# LTC6803.net
KiCad netlist of a schematic drawn in Altium Designer
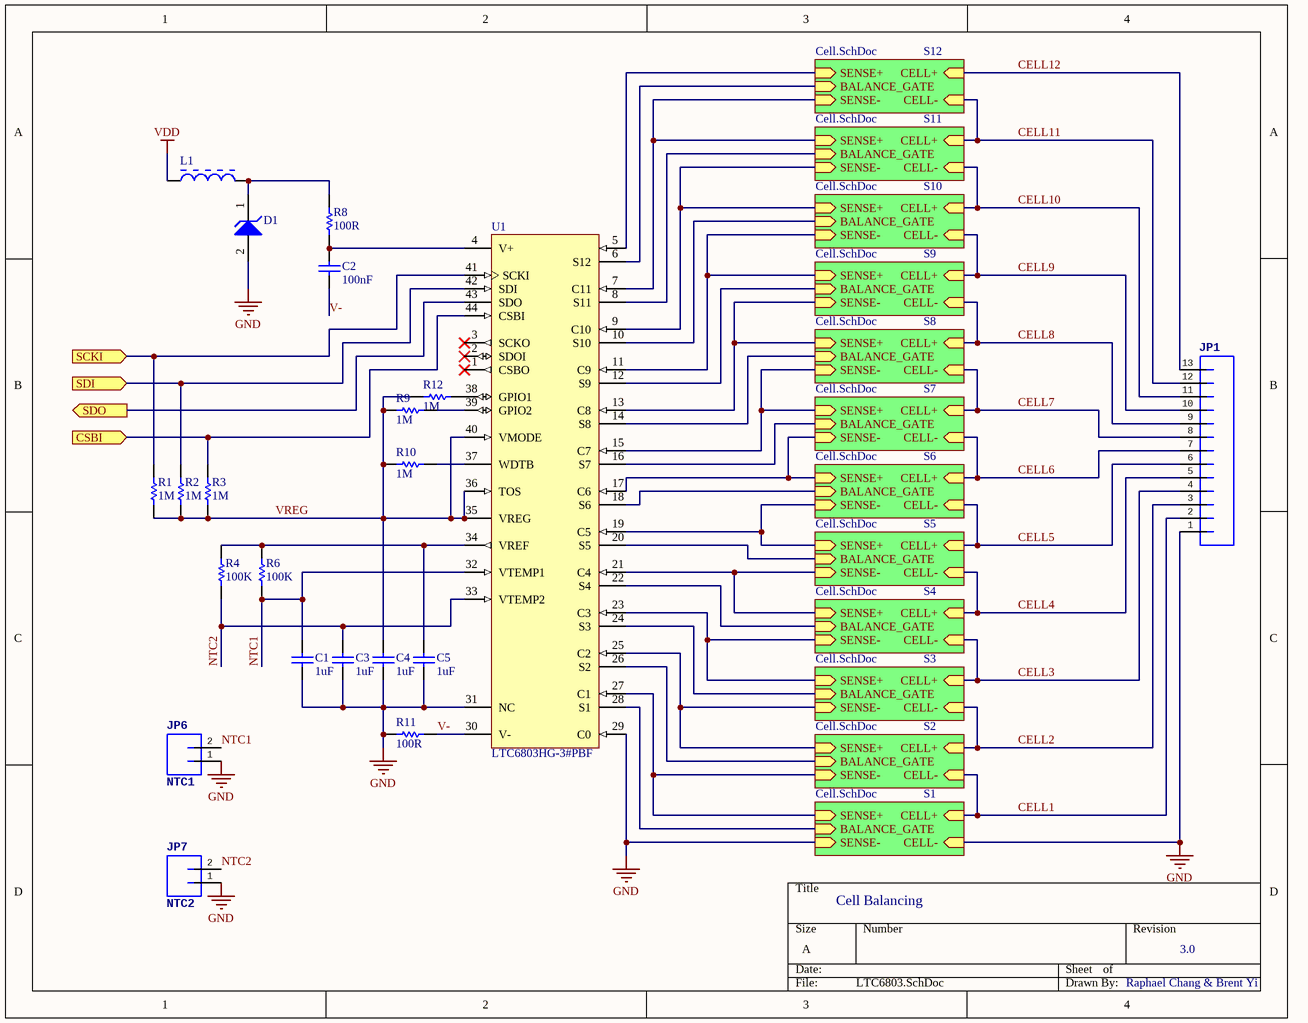
[diagram p0: LTC6803.SchDoc]

(export (version "E")
  (design (tool "Eeschema 10.0.6"))
  (components
    (comp (ref "C1")
      (value "1uF")
      (footprint "CAPC0603(1608)100_N")
      (description "CAP 1uF 6.3V Â±10% 0603 (1608 Metric) Thickness 1mm SMD")
      (fields (field (name "TOLERANCE") "Â±10%"))
      (libsource (lib "Altium Content Vault") (part "CAP"))
    )
    (comp (ref "C2")
      (value "100nF")
      (footprint "CAPC0603(1608)100_L")
      (description "CAP 100nF 100V Â±10% 0603 (1608 Metric) Thickness 1mm SMD")
      (fields (field (name "TOLERANCE") "Â±10%"))
      (libsource (lib "Altium Content Vault") (part "CAP"))
    )
    (comp (ref "C3")
      (value "1uF")
      (footprint "CAPC0603(1608)100_N")
      (description "CAP 1uF 6.3V Â±10% 0603 (1608 Metric) Thickness 1mm SMD")
      (fields (field (name "TOLERANCE") "Â±10%"))
      (libsource (lib "Altium Content Vault") (part "CAP"))
    )
    (comp (ref "C4")
      (value "1uF")
      (footprint "CAPC0603(1608)100_N")
      (description "CAP 1uF 6.3V Â±10% 0603 (1608 Metric) Thickness 1mm SMD")
      (fields (field (name "TOLERANCE") "Â±10%"))
      (libsource (lib "Altium Content Vault") (part "CAP"))
    )
    (comp (ref "C5")
      (value "1uF")
      (footprint "CAPC0603(1608)100_N")
      (description "CAP 1uF 6.3V Â±10% 0603 (1608 Metric) Thickness 1mm SMD")
      (fields (field (name "TOLERANCE") "Â±10%"))
      (libsource (lib "Altium Content Vault") (part "CAP"))
    )
    (comp (ref "D1") (value "~") (footprint "SOD-123") (libsource (lib "Components") (part "CMHZ5265B")))
    (comp (ref "JP1")
      (value "~")
      (footprint "JST-13-PTH-VERT")
      (libsource (lib "Components") (part "JST_XH_13"))
    )
    (comp (ref "JP6")
      (value "NTC1")
      (footprint "JST-2-PTH-VERT")
      (libsource (lib "Components") (part "JST_2_VERT"))
    )
    (comp (ref "JP7")
      (value "NTC2")
      (footprint "JST-2-PTH-VERT")
      (libsource (lib "Components") (part "JST_2_VERT"))
    )
    (comp (ref "L1")
      (value "~")
      (footprint "MURA-BLM31-B60-CHIP-2_V3")
      (libsource (lib "Components") (part "MURA-FB-2"))
    )
    (comp (ref "R1")
      (value "1M")
      (footprint "RESC0603(1608)_L")
      (description "1M 0.1W 1% 0603 (1608 Metric)  SMD")
      (fields (field (name "POWER") "0.1 W") (field (name "TOLERANCE") "1 %"))
      (libsource (lib "Altium Content Vault") (part "RES"))
    )
    (comp (ref "R2")
      (value "1M")
      (footprint "RESC0603(1608)_L")
      (description "1M 0.1W 1% 0603 (1608 Metric)  SMD")
      (fields (field (name "POWER") "0.1 W") (field (name "TOLERANCE") "1 %"))
      (libsource (lib "Altium Content Vault") (part "RES"))
    )
    (comp (ref "R3")
      (value "1M")
      (footprint "RESC0603(1608)_L")
      (description "1M 0.1W 1% 0603 (1608 Metric)  SMD")
      (fields (field (name "POWER") "0.1 W") (field (name "TOLERANCE") "1 %"))
      (libsource (lib "Altium Content Vault") (part "RES"))
    )
    (comp (ref "R4")
      (value "100K")
      (footprint "RESC0603(1608)_N")
      (description "100K 0.1W 5% 0603 (1608 Metric)  SMD")
      (fields (field (name "TOLERANCE") "5 %") (field (name "POWER") "0.1 W"))
      (libsource (lib "Altium Content Vault") (part "RES"))
    )
    (comp (ref "R6")
      (value "100K")
      (footprint "RESC0603(1608)_N")
      (description "100K 0.1W 5% 0603 (1608 Metric)  SMD")
      (fields (field (name "TOLERANCE") "5 %") (field (name "POWER") "0.1 W"))
      (libsource (lib "Altium Content Vault") (part "RES"))
    )
    (comp (ref "R8")
      (value "100R")
      (footprint "RESC0603(1608)_L")
      (description "100R 0.1W 5% 0603 (1608 Metric)  SMD")
      (fields (field (name "TOLERANCE") "5 %") (field (name "POWER") "0.1 W"))
      (libsource (lib "Altium Content Vault") (part "CMP-1012-00050-1"))
    )
    (comp (ref "R9")
      (value "1M")
      (footprint "RESC0603(1608)_L")
      (description "1M 0.1W 1% 0603 (1608 Metric)  SMD")
      (fields (field (name "POWER") "0.1 W") (field (name "TOLERANCE") "1 %"))
      (libsource (lib "Altium Content Vault") (part "RES"))
    )
    (comp (ref "R10")
      (value "1M")
      (footprint "RESC0603(1608)_L")
      (description "1M 0.1W 1% 0603 (1608 Metric)  SMD")
      (fields (field (name "POWER") "0.1 W") (field (name "TOLERANCE") "1 %"))
      (libsource (lib "Altium Content Vault") (part "RES"))
    )
    (comp (ref "R11")
      (value "100R")
      (footprint "RESC0603(1608)_L")
      (description "100R 0.1W 5% 0603 (1608 Metric)  SMD")
      (fields (field (name "TOLERANCE") "5 %") (field (name "POWER") "0.1 W"))
      (libsource (lib "Altium Content Vault") (part "RES"))
    )
    (comp (ref "R12")
      (value "1M")
      (footprint "RESC0603(1608)_L")
      (description "1M 0.1W 1% 0603 (1608 Metric)  SMD")
      (fields (field (name "POWER") "0.1 W") (field (name "TOLERANCE") "1 %"))
      (libsource (lib "Altium Content Vault") (part "RES"))
    )
    (comp (ref "U1")
      (value "LTC6803HG-3#PBF")
      (footprint "LT-G-44_L")
      (description "Multicell Battery Stack Monitor, 60 V Vin MAX, 44-pin SOP (G-44), -40 to 125 degC, Pb-Free")
      (fields (field (name "MANUFACTURER") "Linear Technology"))
      (libsource (lib "Altium Content Vault") (part "LT-LTC6803-3-G-44"))
    )
  )
  (nets
    (net (code "1") (name "/BALANCE_GATE") (class "Default")
      (node (ref "U1") (pin "26") (pinfunction "S2_26") (pintype "tri_state"))
    )
    (net (code "2") (name "/BALANCE_GATE_1") (class "Default")
      (node (ref "U1") (pin "20") (pinfunction "S5_20") (pintype "tri_state"))
    )
    (net (code "3") (name "/BALANCE_GATE_2") (class "Default")
      (node (ref "U1") (pin "18") (pinfunction "S6_18") (pintype "tri_state"))
    )
    (net (code "4") (name "/BALANCE_GATE_3") (class "Default")
      (node (ref "U1") (pin "24") (pinfunction "S3_24") (pintype "tri_state"))
    )
    (net (code "5") (name "/BALANCE_GATE_4") (class "Default")
      (node (ref "U1") (pin "22") (pinfunction "S4_22") (pintype "tri_state"))
    )
    (net (code "6") (name "/BALANCE_GATE_5") (class "Default")
      (node (ref "U1") (pin "6") (pinfunction "S12_6") (pintype "tri_state"))
    )
    (net (code "7") (name "/BALANCE_GATE_6") (class "Default")
      (node (ref "U1") (pin "8") (pinfunction "S11_8") (pintype "tri_state"))
    )
    (net (code "8") (name "/BALANCE_GATE_7") (class "Default")
      (node (ref "U1") (pin "10") (pinfunction "S10_10") (pintype "tri_state"))
    )
    (net (code "9") (name "/BALANCE_GATE_8") (class "Default")
      (node (ref "U1") (pin "12") (pinfunction "S9_12") (pintype "tri_state"))
    )
    (net (code "10") (name "/BALANCE_GATE_9") (class "Default")
      (node (ref "U1") (pin "14") (pinfunction "S8_14") (pintype "tri_state"))
    )
    (net (code "11") (name "/BALANCE_GATE_10") (class "Default")
      (node (ref "U1") (pin "16") (pinfunction "S7_16") (pintype "tri_state"))
    )
    (net (code "12") (name "/BALANCE_GATE_11") (class "Default")
      (node (ref "U1") (pin "28") (pinfunction "S1_28") (pintype "tri_state"))
    )
    (net (code "13") (name "/CELL1") (class "Default")
      (node (ref "JP1") (pin "2") (pinfunction "2_2") (pintype "passive"))
    )
    (net (code "14") (name "/CELL2") (class "Default")
      (node (ref "JP1") (pin "3") (pinfunction "3_3") (pintype "passive"))
    )
    (net (code "15") (name "/CELL3") (class "Default")
      (node (ref "JP1") (pin "4") (pinfunction "4_4") (pintype "passive"))
    )
    (net (code "16") (name "/CELL4") (class "Default")
      (node (ref "JP1") (pin "5") (pinfunction "5_5") (pintype "passive"))
    )
    (net (code "17") (name "/CELL5") (class "Default")
      (node (ref "JP1") (pin "6") (pinfunction "6_6") (pintype "passive"))
    )
    (net (code "18") (name "/CELL6") (class "Default")
      (node (ref "JP1") (pin "7") (pinfunction "7_7") (pintype "passive"))
    )
    (net (code "19") (name "/CELL7") (class "Default")
      (node (ref "JP1") (pin "8") (pinfunction "8_8") (pintype "passive"))
    )
    (net (code "20") (name "/CELL8") (class "Default")
      (node (ref "JP1") (pin "9") (pinfunction "9_9") (pintype "passive"))
    )
    (net (code "21") (name "/CELL9") (class "Default")
      (node (ref "JP1") (pin "10") (pinfunction "10_10") (pintype "passive"))
    )
    (net (code "22") (name "/CELL10") (class "Default")
      (node (ref "JP1") (pin "11") (pinfunction "11_11") (pintype "passive"))
    )
    (net (code "23") (name "/CELL11") (class "Default")
      (node (ref "JP1") (pin "12") (pinfunction "12_12") (pintype "passive"))
    )
    (net (code "24") (name "/CELL12") (class "Default")
      (node (ref "JP1") (pin "13") (pinfunction "13_13") (pintype "passive"))
    )
    (net (code "25") (name "/CSBI") (class "Default")
      (node (ref "R3") (pin "2") (pinfunction "2_2") (pintype "passive"))
      (node (ref "U1") (pin "44") (pinfunction "CSBI_44") (pintype "input"))
    )
    (net (code "26") (name "/NTC1") (class "Default")
      (node (ref "C1") (pin "2") (pinfunction "2_2") (pintype "passive"))
      (node (ref "JP6") (pin "2") (pinfunction "2_2") (pintype "passive"))
      (node (ref "R6") (pin "1") (pinfunction "1_1") (pintype "passive"))
      (node (ref "U1") (pin "32") (pinfunction "VTEMP1_32") (pintype "input"))
    )
    (net (code "27") (name "/NTC2") (class "Default")
      (node (ref "C3") (pin "2") (pinfunction "2_2") (pintype "passive"))
      (node (ref "JP7") (pin "2") (pinfunction "2_2") (pintype "passive"))
      (node (ref "R4") (pin "1") (pinfunction "1_1") (pintype "passive"))
      (node (ref "U1") (pin "33") (pinfunction "VTEMP2_33") (pintype "input"))
    )
    (net (code "28") (name "/SCKI") (class "Default")
      (node (ref "R1") (pin "2") (pinfunction "2_2") (pintype "passive"))
      (node (ref "U1") (pin "41") (pinfunction "SCKI_41") (pintype "input"))
    )
    (net (code "29") (name "/SDI") (class "Default")
      (node (ref "R2") (pin "2") (pinfunction "2_2") (pintype "passive"))
      (node (ref "U1") (pin "42") (pinfunction "SDI_42") (pintype "input"))
    )
    (net (code "30") (name "/SDO") (class "Default")
      (node (ref "U1") (pin "43") (pinfunction "SDO_43") (pintype "open_collector"))
    )
    (net (code "31") (name "/SENSE+") (class "Default")
      (node (ref "U1") (pin "27") (pinfunction "C1_27") (pintype "input"))
    )
    (net (code "32") (name "/SENSE+_1") (class "Default")
      (node (ref "U1") (pin "17") (pinfunction "C6_17") (pintype "input"))
    )
    (net (code "33") (name "/SENSE+_2") (class "Default")
      (node (ref "U1") (pin "19") (pinfunction "C5_19") (pintype "input"))
    )
    (net (code "34") (name "/SENSE+_3") (class "Default")
      (node (ref "U1") (pin "25") (pinfunction "C2_25") (pintype "input"))
    )
    (net (code "35") (name "/SENSE+_4") (class "Default")
      (node (ref "U1") (pin "23") (pinfunction "C3_23") (pintype "input"))
    )
    (net (code "36") (name "/SENSE+_5") (class "Default")
      (node (ref "U1") (pin "21") (pinfunction "C4_21") (pintype "input"))
    )
    (net (code "37") (name "/SENSE+_6") (class "Default") (node (ref "U1") (pin "5") (pintype "input")))
    (net (code "38") (name "/SENSE+_7") (class "Default")
      (node (ref "U1") (pin "7") (pinfunction "C11_7") (pintype "input"))
    )
    (net (code "39") (name "/SENSE+_8") (class "Default")
      (node (ref "U1") (pin "9") (pinfunction "C10_9") (pintype "input"))
    )
    (net (code "40") (name "/SENSE+_9") (class "Default")
      (node (ref "U1") (pin "11") (pinfunction "C9_11") (pintype "input"))
    )
    (net (code "41") (name "/SENSE+_10") (class "Default")
      (node (ref "U1") (pin "13") (pinfunction "C8_13") (pintype "input"))
    )
    (net (code "42") (name "/SENSE+_11") (class "Default")
      (node (ref "U1") (pin "15") (pinfunction "C7_15") (pintype "input"))
    )
    (net (code "43") (name "/V-") (class "Default")
      (node (ref "C2") (pin "1") (pinfunction "1_1") (pintype "passive"))
      (node (ref "R11") (pin "2") (pinfunction "2_2") (pintype "passive"))
      (node (ref "U1") (pin "30") (pinfunction "V-_30") (pintype "power_in"))
    )
    (net (code "44") (name "/VREG") (class "Default")
      (node (ref "C4") (pin "2") (pinfunction "2_2") (pintype "passive"))
      (node (ref "R1") (pin "1") (pinfunction "1_1") (pintype "passive"))
      (node (ref "R10") (pin "1") (pinfunction "1_1") (pintype "passive"))
      (node (ref "R12") (pin "1") (pinfunction "1_1") (pintype "passive"))
      (node (ref "R2") (pin "1") (pinfunction "1_1") (pintype "passive"))
      (node (ref "R3") (pin "1") (pinfunction "1_1") (pintype "passive"))
      (node (ref "R9") (pin "1") (pinfunction "1_1") (pintype "passive"))
      (node (ref "U1") (pin "35") (pinfunction "VREG_35") (pintype "power_in"))
      (node (ref "U1") (pin "36") (pinfunction "TOS_36") (pintype "input"))
      (node (ref "U1") (pin "40") (pinfunction "VMODE_40") (pintype "input"))
    )
    (net (code "45") (name "GND") (class "Default")
      (node (ref "C1") (pin "1") (pinfunction "1_1") (pintype "passive"))
      (node (ref "C3") (pin "1") (pinfunction "1_1") (pintype "passive"))
      (node (ref "C4") (pin "1") (pinfunction "1_1") (pintype "passive"))
      (node (ref "C5") (pin "1") (pinfunction "1_1") (pintype "passive"))
      (node (ref "D1") (pin "2") (pinfunction "A_2") (pintype "passive"))
      (node (ref "JP1") (pin "1") (pinfunction "1_1") (pintype "passive"))
      (node (ref "JP6") (pin "1") (pinfunction "1_1") (pintype "passive"))
      (node (ref "JP7") (pin "1") (pinfunction "1_1") (pintype "passive"))
      (node (ref "R11") (pin "1") (pinfunction "1_1") (pintype "passive"))
      (node (ref "U1") (pin "29") (pinfunction "C0_29") (pintype "input"))
      (node (ref "U1") (pin "31") (pinfunction "NC_31") (pintype "passive"))
    )
    (net (code "46") (name "Net-(D1-K)") (class "Default")
      (node (ref "D1") (pin "1") (pinfunction "K_1") (pintype "passive"))
      (node (ref "L1") (pin "2") (pinfunction "2_2") (pintype "passive"))
      (node (ref "R8") (pin "2") (pinfunction "2_2") (pintype "passive"))
    )
    (net (code "47") (name "Net-(U1-GPIO1)") (class "Default")
      (node (ref "R12") (pin "2") (pinfunction "2_2") (pintype "passive"))
      (node (ref "U1") (pin "38") (pinfunction "GPIO1_38") (pintype "bidirectional"))
    )
    (net (code "48") (name "Net-(U1-GPIO2)") (class "Default")
      (node (ref "R9") (pin "2") (pinfunction "2_2") (pintype "passive"))
      (node (ref "U1") (pin "39") (pinfunction "GPIO2_39") (pintype "bidirectional"))
    )
    (net (code "49") (name "Net-(U1-V+)") (class "Default")
      (node (ref "C2") (pin "2") (pinfunction "2_2") (pintype "passive"))
      (node (ref "R8") (pin "1") (pinfunction "1_1") (pintype "passive"))
      (node (ref "U1") (pin "4") (pinfunction "V+_4") (pintype "power_in"))
    )
    (net (code "50") (name "Net-(U1-VREF)") (class "Default")
      (node (ref "C5") (pin "2") (pinfunction "2_2") (pintype "passive"))
      (node (ref "R4") (pin "2") (pinfunction "2_2") (pintype "passive"))
      (node (ref "R6") (pin "2") (pinfunction "2_2") (pintype "passive"))
      (node (ref "U1") (pin "34") (pinfunction "VREF_34") (pintype "output"))
    )
    (net (code "51") (name "Net-(U1-WDTB)") (class "Default")
      (node (ref "R10") (pin "2") (pinfunction "2_2") (pintype "passive"))
      (node (ref "U1") (pin "37") (pinfunction "WDTB_37") (pintype "open_collector"))
    )
    (net (code "52") (name "VDD") (class "Default")
      (node (ref "L1") (pin "1") (pinfunction "1_1") (pintype "passive"))
    )
    (net (code "53") (name "unconnected-(U1-CSBO-Pad1)") (class "Default")
      (node (ref "U1") (pin "1") (pinfunction "CSBO_1") (pintype "output+no_connect"))
    )
    (net (code "54") (name "unconnected-(U1-SCKO-Pad3)") (class "Default")
      (node (ref "U1") (pin "3") (pinfunction "SCKO_3") (pintype "output+no_connect"))
    )
    (net (code "55") (name "unconnected-(U1-SDOI-Pad2)") (class "Default")
      (node (ref "U1") (pin "2") (pinfunction "SDOI_2") (pintype "bidirectional+no_connect"))
    )
  )
)
